# Serial_IO_Interface1.net
KiCad netlist of a schematic drawn in Altium Designer
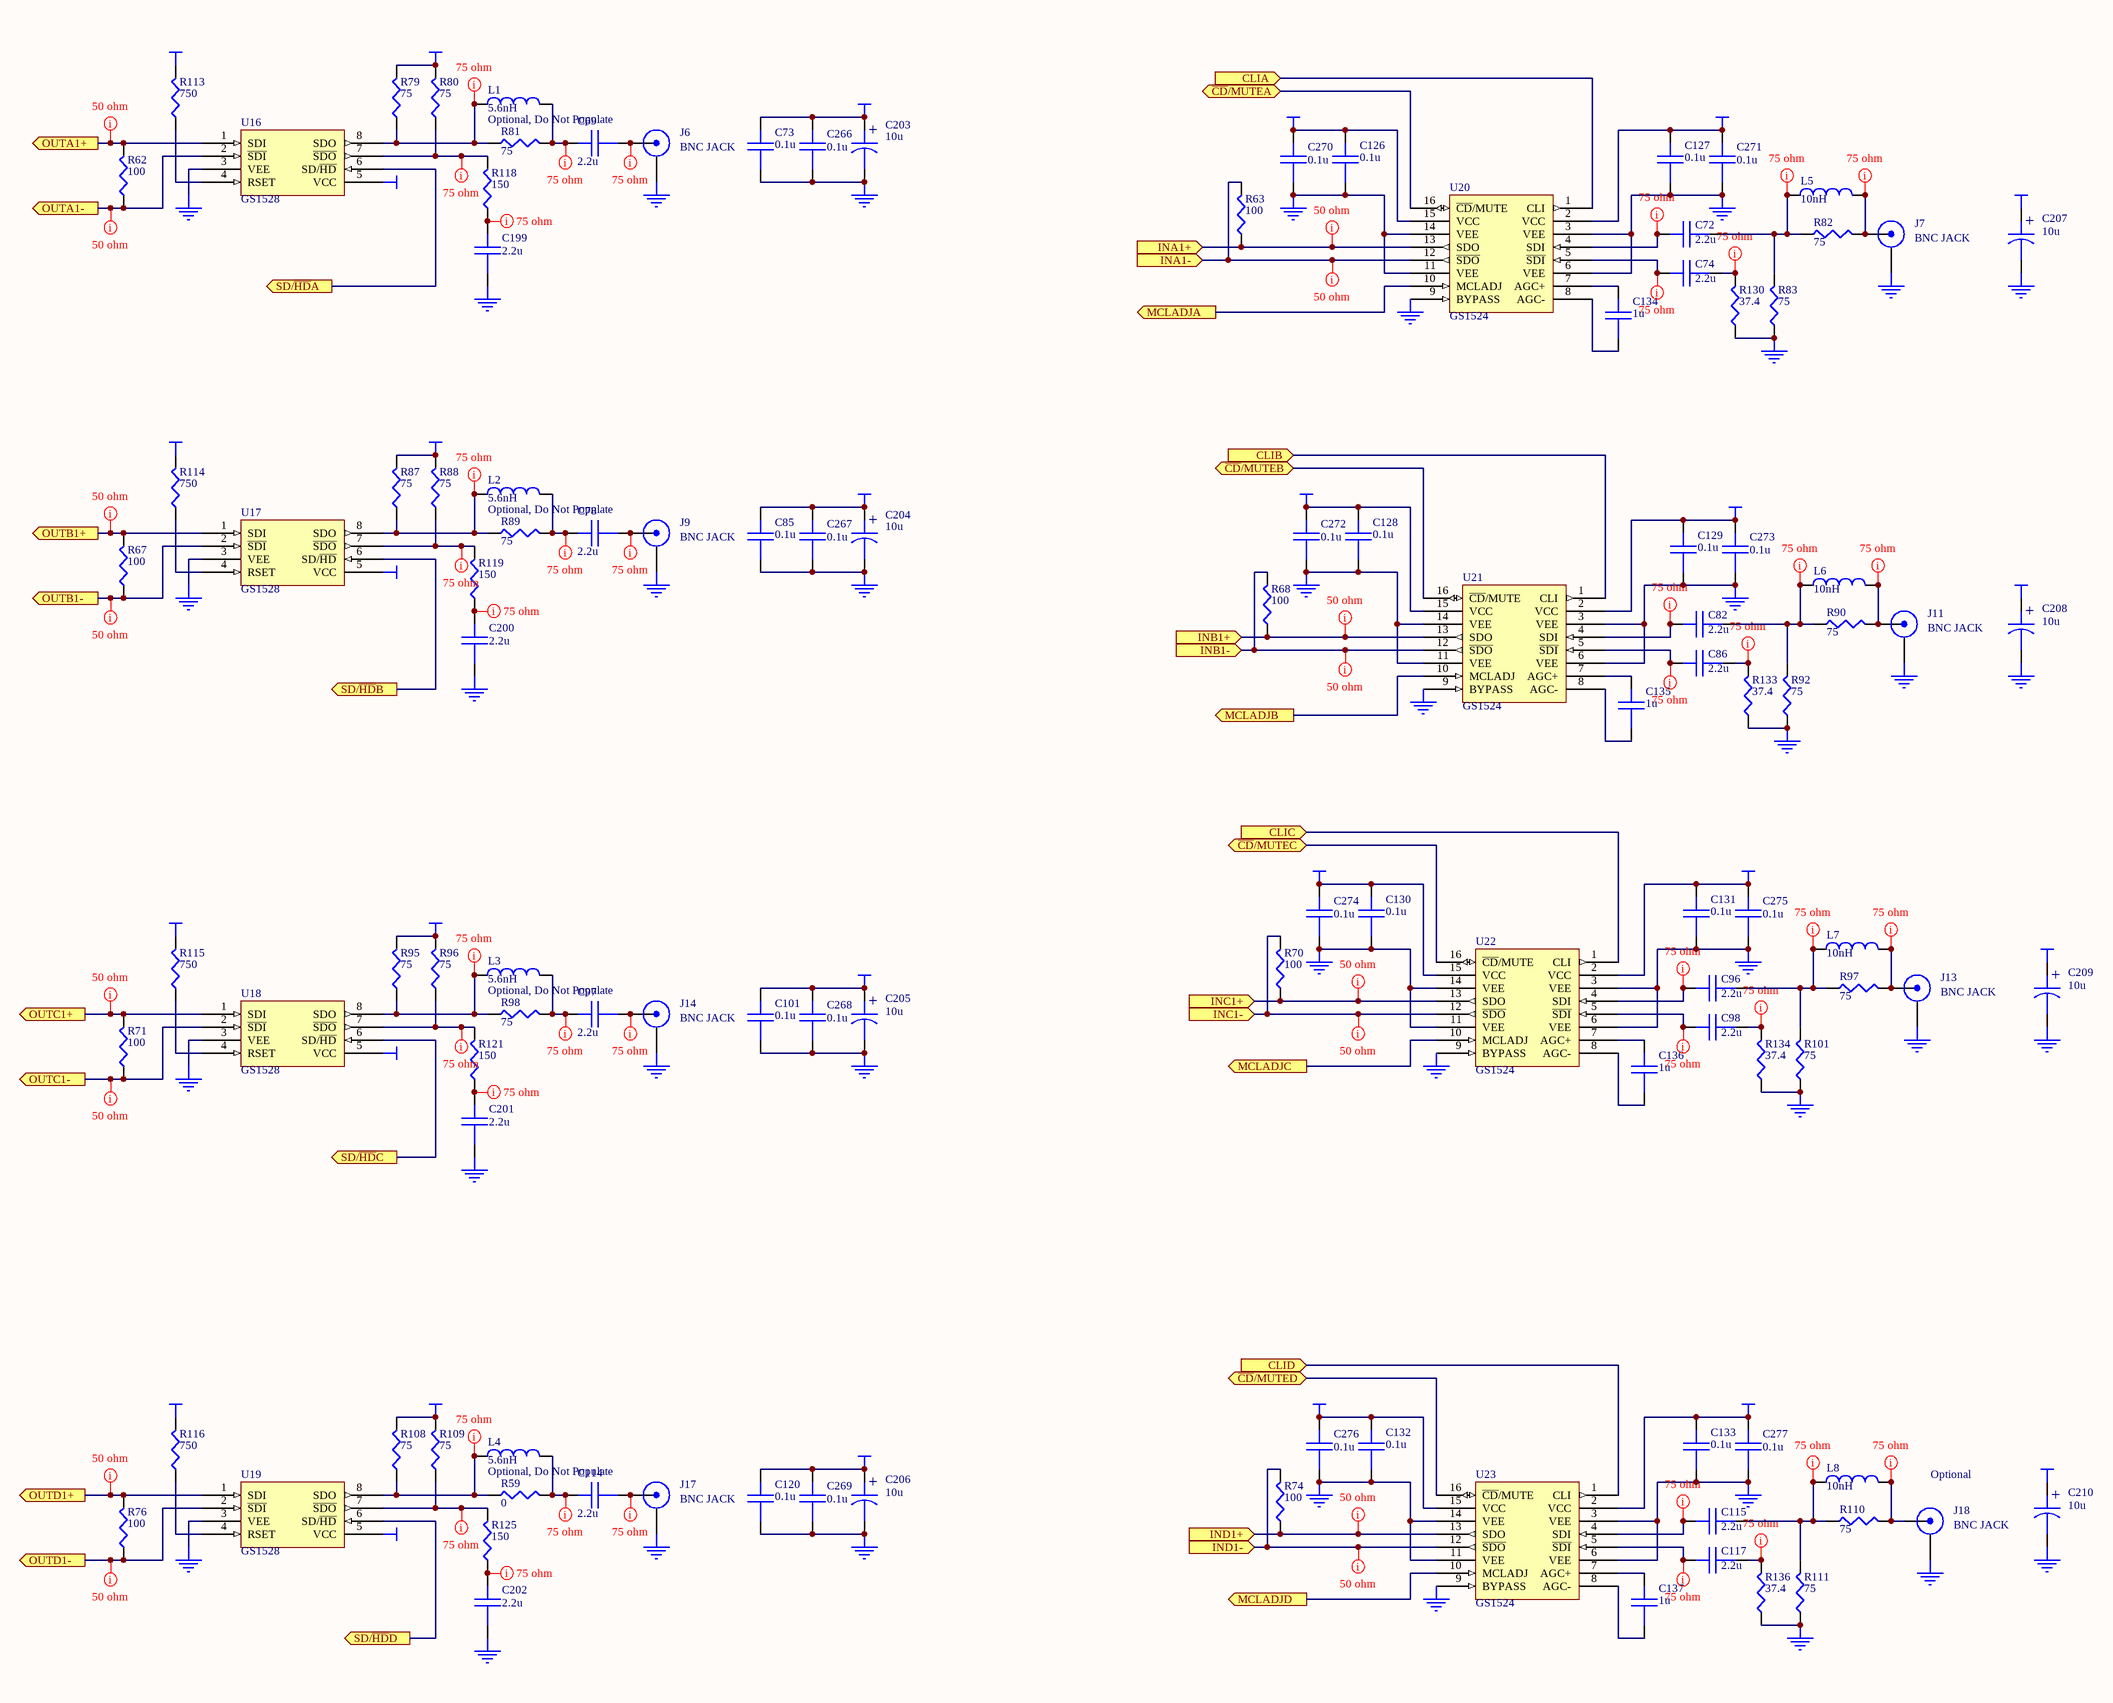
[diagram p0: Serial IO Interface1.SchDoc]

(export (version "E")
  (design (tool "Eeschema 10.0.6"))
  (components
    (comp (ref "C69")
      (value "~")
      (footprint "0603")
      (description "SMT CAP")
      (libsource (lib "Cypress Molson") (part "CAP"))
    )
    (comp (ref "C72")
      (value "~")
      (footprint "0603")
      (description "SMT CAP")
      (libsource (lib "Cypress Molson") (part "CAP"))
    )
    (comp (ref "C73")
      (value "~")
      (footprint "0603")
      (description "SMT CAP")
      (libsource (lib "Cypress Molson") (part "CAP"))
    )
    (comp (ref "C74")
      (value "~")
      (footprint "0603")
      (description "SMT CAP")
      (libsource (lib "Cypress Molson") (part "CAP"))
    )
    (comp (ref "C78")
      (value "~")
      (footprint "0603")
      (description "SMT CAP")
      (libsource (lib "Cypress Molson") (part "CAP"))
    )
    (comp (ref "C82")
      (value "~")
      (footprint "0603")
      (description "SMT CAP")
      (libsource (lib "Cypress Molson") (part "CAP"))
    )
    (comp (ref "C85")
      (value "~")
      (footprint "0603")
      (description "SMT CAP")
      (libsource (lib "Cypress Molson") (part "CAP"))
    )
    (comp (ref "C86")
      (value "~")
      (footprint "0603")
      (description "SMT CAP")
      (libsource (lib "Cypress Molson") (part "CAP"))
    )
    (comp (ref "C96")
      (value "~")
      (footprint "0603")
      (description "SMT CAP")
      (libsource (lib "Cypress Molson") (part "CAP"))
    )
    (comp (ref "C97")
      (value "~")
      (footprint "0603")
      (description "SMT CAP")
      (libsource (lib "Cypress Molson") (part "CAP"))
    )
    (comp (ref "C98")
      (value "~")
      (footprint "0603")
      (description "SMT CAP")
      (libsource (lib "Cypress Molson") (part "CAP"))
    )
    (comp (ref "C101")
      (value "~")
      (footprint "0603")
      (description "SMT CAP")
      (libsource (lib "Cypress Molson") (part "CAP"))
    )
    (comp (ref "C114")
      (value "~")
      (footprint "0603")
      (description "SMT CAP")
      (libsource (lib "Cypress Molson") (part "CAP"))
    )
    (comp (ref "C115")
      (value "~")
      (footprint "0603")
      (description "SMT CAP")
      (libsource (lib "Cypress Molson") (part "CAP"))
    )
    (comp (ref "C117")
      (value "~")
      (footprint "0603")
      (description "SMT CAP")
      (libsource (lib "Cypress Molson") (part "CAP"))
    )
    (comp (ref "C120")
      (value "~")
      (footprint "0603")
      (description "SMT CAP")
      (libsource (lib "Cypress Molson") (part "CAP"))
    )
    (comp (ref "C126")
      (value "0.1u")
      (footprint "0603")
      (description "SMT CAP")
      (libsource (lib "Schematic") (part "CAP"))
    )
    (comp (ref "C127")
      (value "0.1u")
      (footprint "0603")
      (description "SMT CAP")
      (libsource (lib "Schematic") (part "CAP"))
    )
    (comp (ref "C128")
      (value "0.1u")
      (footprint "0603")
      (description "SMT CAP")
      (libsource (lib "Schematic") (part "CAP"))
    )
    (comp (ref "C129")
      (value "0.1u")
      (footprint "0603")
      (description "SMT CAP")
      (libsource (lib "Schematic") (part "CAP"))
    )
    (comp (ref "C130")
      (value "0.1u")
      (footprint "0603")
      (description "SMT CAP")
      (libsource (lib "Schematic") (part "CAP"))
    )
    (comp (ref "C131")
      (value "0.1u")
      (footprint "0603")
      (description "SMT CAP")
      (libsource (lib "Schematic") (part "CAP"))
    )
    (comp (ref "C132")
      (value "0.1u")
      (footprint "0603")
      (description "SMT CAP")
      (libsource (lib "Schematic") (part "CAP"))
    )
    (comp (ref "C133")
      (value "0.1u")
      (footprint "0603")
      (description "SMT CAP")
      (libsource (lib "Schematic") (part "CAP"))
    )
    (comp (ref "C134")
      (value "1u")
      (footprint "0603")
      (description "SMT CAP")
      (libsource (lib "Schematic") (part "CAP"))
    )
    (comp (ref "C135")
      (value "1u")
      (footprint "0603")
      (description "SMT CAP")
      (libsource (lib "Schematic") (part "CAP"))
    )
    (comp (ref "C136")
      (value "1u")
      (footprint "0603")
      (description "SMT CAP")
      (libsource (lib "Schematic") (part "CAP"))
    )
    (comp (ref "C137")
      (value "1u")
      (footprint "0603")
      (description "SMT CAP")
      (libsource (lib "Schematic") (part "CAP"))
    )
    (comp (ref "C199")
      (value "~")
      (footprint "0603")
      (description "SMT CAP")
      (libsource (lib "Cypress Molson") (part "CAP"))
    )
    (comp (ref "C200")
      (value "~")
      (footprint "0603")
      (description "SMT CAP")
      (libsource (lib "Cypress Molson") (part "CAP"))
    )
    (comp (ref "C201")
      (value "~")
      (footprint "0603")
      (description "SMT CAP")
      (libsource (lib "Cypress Molson") (part "CAP"))
    )
    (comp (ref "C202")
      (value "~")
      (footprint "0603")
      (description "SMT CAP")
      (libsource (lib "Cypress Molson") (part "CAP"))
    )
    (comp (ref "C203")
      (value "10u")
      (footprint "6032")
      (libsource (lib "Cypress Molson") (part "CAPACITOR POL"))
    )
    (comp (ref "C204")
      (value "10u")
      (footprint "6032")
      (libsource (lib "Cypress Molson") (part "CAPACITOR POL"))
    )
    (comp (ref "C205")
      (value "10u")
      (footprint "6032")
      (libsource (lib "Cypress Molson") (part "CAPACITOR POL"))
    )
    (comp (ref "C206")
      (value "10u")
      (footprint "6032")
      (libsource (lib "Cypress Molson") (part "CAPACITOR POL"))
    )
    (comp (ref "C207")
      (value "10u")
      (footprint "6032")
      (libsource (lib "Cypress Molson") (part "CAPACITOR POL"))
    )
    (comp (ref "C208")
      (value "10u")
      (footprint "6032")
      (libsource (lib "Cypress Molson") (part "CAPACITOR POL"))
    )
    (comp (ref "C209")
      (value "10u")
      (footprint "6032")
      (libsource (lib "Cypress Molson") (part "CAPACITOR POL"))
    )
    (comp (ref "C210")
      (value "10u")
      (footprint "6032")
      (libsource (lib "Cypress Molson") (part "CAPACITOR POL"))
    )
    (comp (ref "C266")
      (value "~")
      (footprint "0603")
      (description "SMT CAP")
      (libsource (lib "Cypress Molson") (part "CAP"))
    )
    (comp (ref "C267")
      (value "~")
      (footprint "0603")
      (description "SMT CAP")
      (libsource (lib "Cypress Molson") (part "CAP"))
    )
    (comp (ref "C268")
      (value "~")
      (footprint "0603")
      (description "SMT CAP")
      (libsource (lib "Cypress Molson") (part "CAP"))
    )
    (comp (ref "C269")
      (value "~")
      (footprint "0603")
      (description "SMT CAP")
      (libsource (lib "Cypress Molson") (part "CAP"))
    )
    (comp (ref "C270")
      (value "~")
      (footprint "0603")
      (description "SMT CAP")
      (libsource (lib "Cypress Molson") (part "CAP"))
    )
    (comp (ref "C271")
      (value "~")
      (footprint "0603")
      (description "SMT CAP")
      (libsource (lib "Cypress Molson") (part "CAP"))
    )
    (comp (ref "C272")
      (value "~")
      (footprint "0603")
      (description "SMT CAP")
      (libsource (lib "Cypress Molson") (part "CAP"))
    )
    (comp (ref "C273")
      (value "~")
      (footprint "0603")
      (description "SMT CAP")
      (libsource (lib "Cypress Molson") (part "CAP"))
    )
    (comp (ref "C274")
      (value "~")
      (footprint "0603")
      (description "SMT CAP")
      (libsource (lib "Cypress Molson") (part "CAP"))
    )
    (comp (ref "C275")
      (value "~")
      (footprint "0603")
      (description "SMT CAP")
      (libsource (lib "Cypress Molson") (part "CAP"))
    )
    (comp (ref "C276")
      (value "~")
      (footprint "0603")
      (description "SMT CAP")
      (libsource (lib "Cypress Molson") (part "CAP"))
    )
    (comp (ref "C277")
      (value "~")
      (footprint "0603")
      (description "SMT CAP")
      (libsource (lib "Cypress Molson") (part "CAP"))
    )
    (comp (ref "J6")
      (value "BNC JACK")
      (footprint "BNC-EDGE")
      (description "BNC Jack")
      (libsource (lib "Cypress Molson") (part "BNC JACK"))
    )
    (comp (ref "J7")
      (value "BNC JACK")
      (footprint "BNC-EDGE")
      (description "BNC Jack")
      (libsource (lib "Cypress Molson") (part "BNC JACK"))
    )
    (comp (ref "J9")
      (value "BNC JACK")
      (footprint "BNC-EDGE")
      (description "BNC Jack")
      (libsource (lib "Cypress Molson") (part "BNC JACK"))
    )
    (comp (ref "J11")
      (value "BNC JACK")
      (footprint "BNC-EDGE")
      (description "BNC Jack")
      (libsource (lib "Cypress Molson") (part "BNC JACK"))
    )
    (comp (ref "J13")
      (value "BNC JACK")
      (footprint "BNC-EDGE")
      (description "BNC Jack")
      (libsource (lib "Cypress Molson") (part "BNC JACK"))
    )
    (comp (ref "J14")
      (value "BNC JACK")
      (footprint "BNC-EDGE")
      (description "BNC Jack")
      (libsource (lib "Cypress Molson") (part "BNC JACK"))
    )
    (comp (ref "J17")
      (value "BNC JACK")
      (footprint "BNC-EDGE")
      (description "BNC Jack")
      (libsource (lib "Cypress Molson") (part "BNC JACK"))
    )
    (comp (ref "J18")
      (value "BNC JACK")
      (footprint "BNC-EDGE")
      (description "BNC Jack")
      (libsource (lib "Cypress Molson") (part "BNC JACK"))
    )
    (comp (ref "L1")
      (value "5.6nH")
      (footprint "0805")
      (description "Inductor")
      (fields
        (field (name "MANUFACTURER") "Generic Components")
        (field (name "NOTE") "Optional, Do Not Populate")
        (field (name "PUBLISHER") "Altium Limited")
      )
      (libsource (lib "Miscellaneous Devices") (part "Inductor"))
    )
    (comp (ref "L2")
      (value "5.6nH")
      (footprint "0805")
      (description "Inductor")
      (fields
        (field (name "MANUFACTURER") "Generic Components")
        (field (name "NOTE") "Optional, Do Not Populate")
        (field (name "PUBLISHER") "Altium Limited")
      )
      (libsource (lib "Miscellaneous Devices") (part "Inductor"))
    )
    (comp (ref "L3")
      (value "5.6nH")
      (footprint "0805")
      (description "Inductor")
      (fields
        (field (name "MANUFACTURER") "Generic Components")
        (field (name "NOTE") "Optional, Do Not Populate")
        (field (name "PUBLISHER") "Altium Limited")
      )
      (libsource (lib "Miscellaneous Devices") (part "Inductor"))
    )
    (comp (ref "L4")
      (value "5.6nH")
      (footprint "0805")
      (description "Inductor")
      (fields
        (field (name "MANUFACTURER") "Generic Components")
        (field (name "NOTE") "Optional, Do Not Populate")
        (field (name "PUBLISHER") "Altium Limited")
      )
      (libsource (lib "Miscellaneous Devices") (part "Inductor"))
    )
    (comp (ref "L5")
      (value "10nH")
      (footprint "0805")
      (description "Inductor")
      (fields (field (name "MANUFACTURER") "Generic Components") (field (name "PUBLISHER") "Altium Limited"))
      (libsource (lib "Miscellaneous Devices") (part "Inductor"))
    )
    (comp (ref "L6")
      (value "10nH")
      (footprint "0805")
      (description "Inductor")
      (fields (field (name "MANUFACTURER") "Generic Components") (field (name "PUBLISHER") "Altium Limited"))
      (libsource (lib "Miscellaneous Devices") (part "Inductor"))
    )
    (comp (ref "L7")
      (value "10nH")
      (footprint "0805")
      (description "Inductor")
      (fields (field (name "MANUFACTURER") "Generic Components") (field (name "PUBLISHER") "Altium Limited"))
      (libsource (lib "Miscellaneous Devices") (part "Inductor"))
    )
    (comp (ref "L8")
      (value "10nH")
      (footprint "0805")
      (description "Inductor")
      (fields (field (name "MANUFACTURER") "Generic Components") (field (name "PUBLISHER") "Altium Limited"))
      (libsource (lib "Miscellaneous Devices") (part "Inductor"))
    )
    (comp (ref "R59") (value "0") (footprint "0603") (libsource (lib "Cypress Molson") (part "RES1")))
    (comp (ref "R62") (value "100") (footprint "0603") (libsource (lib "Cypress Molson") (part "RES1")))
    (comp (ref "R63") (value "100") (footprint "0603") (libsource (lib "Cypress Molson") (part "RES1")))
    (comp (ref "R67") (value "100") (footprint "0603") (libsource (lib "Cypress Molson") (part "RES1")))
    (comp (ref "R68") (value "100") (footprint "0603") (libsource (lib "Cypress Molson") (part "RES1")))
    (comp (ref "R70") (value "100") (footprint "0603") (libsource (lib "Cypress Molson") (part "RES1")))
    (comp (ref "R71") (value "100") (footprint "0603") (libsource (lib "Cypress Molson") (part "RES1")))
    (comp (ref "R74") (value "100") (footprint "0603") (libsource (lib "Cypress Molson") (part "RES1")))
    (comp (ref "R76") (value "100") (footprint "0603") (libsource (lib "Cypress Molson") (part "RES1")))
    (comp (ref "R79") (value "75") (footprint "0603") (libsource (lib "Cypress Molson") (part "RES1")))
    (comp (ref "R80") (value "75") (footprint "0603") (libsource (lib "Cypress Molson") (part "RES1")))
    (comp (ref "R81") (value "75") (footprint "0603") (libsource (lib "Cypress Molson") (part "RES1")))
    (comp (ref "R82") (value "75") (footprint "0603") (libsource (lib "Cypress Molson") (part "RES1")))
    (comp (ref "R83") (value "75") (footprint "0603") (libsource (lib "Cypress Molson") (part "RES1")))
    (comp (ref "R87") (value "75") (footprint "0603") (libsource (lib "Cypress Molson") (part "RES1")))
    (comp (ref "R88") (value "75") (footprint "0603") (libsource (lib "Cypress Molson") (part "RES1")))
    (comp (ref "R89") (value "75") (footprint "0603") (libsource (lib "Cypress Molson") (part "RES1")))
    (comp (ref "R90") (value "75") (footprint "0603") (libsource (lib "Cypress Molson") (part "RES1")))
    (comp (ref "R92") (value "75") (footprint "0603") (libsource (lib "Cypress Molson") (part "RES1")))
    (comp (ref "R95") (value "75") (footprint "0603") (libsource (lib "Cypress Molson") (part "RES1")))
    (comp (ref "R96") (value "75") (footprint "0603") (libsource (lib "Cypress Molson") (part "RES1")))
    (comp (ref "R97") (value "75") (footprint "0603") (libsource (lib "Cypress Molson") (part "RES1")))
    (comp (ref "R98") (value "75") (footprint "0603") (libsource (lib "Cypress Molson") (part "RES1")))
    (comp (ref "R101") (value "75") (footprint "0603") (libsource (lib "Cypress Molson") (part "RES1")))
    (comp (ref "R108") (value "75") (footprint "0603") (libsource (lib "Cypress Molson") (part "RES1")))
    (comp (ref "R109") (value "75") (footprint "0603") (libsource (lib "Cypress Molson") (part "RES1")))
    (comp (ref "R110") (value "75") (footprint "0603") (libsource (lib "Cypress Molson") (part "RES1")))
    (comp (ref "R111") (value "75") (footprint "0603") (libsource (lib "Cypress Molson") (part "RES1")))
    (comp (ref "R113") (value "750") (footprint "0603") (libsource (lib "Cypress Molson") (part "RES1")))
    (comp (ref "R114") (value "750") (footprint "0603") (libsource (lib "Cypress Molson") (part "RES1")))
    (comp (ref "R115") (value "750") (footprint "0603") (libsource (lib "Cypress Molson") (part "RES1")))
    (comp (ref "R116") (value "750") (footprint "0603") (libsource (lib "Cypress Molson") (part "RES1")))
    (comp (ref "R118") (value "150") (footprint "0603") (libsource (lib "Cypress Molson") (part "RES1")))
    (comp (ref "R119") (value "150") (footprint "0603") (libsource (lib "Cypress Molson") (part "RES1")))
    (comp (ref "R121") (value "150") (footprint "0603") (libsource (lib "Cypress Molson") (part "RES1")))
    (comp (ref "R125") (value "150") (footprint "0603") (libsource (lib "Cypress Molson") (part "RES1")))
    (comp (ref "R130") (value "37.4") (footprint "0603") (libsource (lib "Cypress Molson") (part "RES1")))
    (comp (ref "R133") (value "37.4") (footprint "0603") (libsource (lib "Cypress Molson") (part "RES1")))
    (comp (ref "R134") (value "37.4") (footprint "0603") (libsource (lib "Cypress Molson") (part "RES1")))
    (comp (ref "R136") (value "37.4") (footprint "0603") (libsource (lib "Cypress Molson") (part "RES1")))
    (comp (ref "U16")
      (value "GS1528")
      (footprint "SO-8")
      (description "HD-LINX II Multi-Rate SDI Dual Slew-Rate Cable Driver")
      (libsource (lib "Cypress Molson") (part "GS1528"))
    )
    (comp (ref "U17")
      (value "GS1528")
      (footprint "SO-8")
      (description "HD-LINX II Multi-Rate SDI Dual Slew-Rate Cable Driver")
      (libsource (lib "Cypress Molson") (part "GS1528"))
    )
    (comp (ref "U18")
      (value "GS1528")
      (footprint "SO-8")
      (description "HD-LINX II Multi-Rate SDI Dual Slew-Rate Cable Driver")
      (libsource (lib "Cypress Molson") (part "GS1528"))
    )
    (comp (ref "U19")
      (value "GS1528")
      (footprint "SO-8")
      (description "HD-LINX II Multi-Rate SDI Dual Slew-Rate Cable Driver")
      (libsource (lib "Cypress Molson") (part "GS1528"))
    )
    (comp (ref "U20")
      (value "GS1524")
      (footprint "SO-16")
      (description "HD-LINX II Multi-Rate SDI Adaptive Cable Equalizer")
      (libsource (lib "Cypress Molson") (part "GS1524"))
    )
    (comp (ref "U21")
      (value "GS1524")
      (footprint "SO-16")
      (description "HD-LINX II Multi-Rate SDI Adaptive Cable Equalizer")
      (libsource (lib "Cypress Molson") (part "GS1524"))
    )
    (comp (ref "U22")
      (value "GS1524")
      (footprint "SO-16")
      (description "HD-LINX II Multi-Rate SDI Adaptive Cable Equalizer")
      (libsource (lib "Cypress Molson") (part "GS1524"))
    )
    (comp (ref "U23")
      (value "GS1524")
      (footprint "SO-16")
      (description "HD-LINX II Multi-Rate SDI Adaptive Cable Equalizer")
      (libsource (lib "Cypress Molson") (part "GS1524"))
    )
  )
  (nets
    (net (code "1") (name "+3.3V") (class "Default")
      (node (ref "C101") (pin "1") (pinfunction "1_1") (pintype "passive"))
      (node (ref "C120") (pin "1") (pinfunction "1_1") (pintype "passive"))
      (node (ref "C126") (pin "1") (pinfunction "1_1") (pintype "passive"))
      (node (ref "C127") (pin "1") (pinfunction "1_1") (pintype "passive"))
      (node (ref "C128") (pin "1") (pinfunction "1_1") (pintype "passive"))
      (node (ref "C129") (pin "1") (pinfunction "1_1") (pintype "passive"))
      (node (ref "C130") (pin "1") (pinfunction "1_1") (pintype "passive"))
      (node (ref "C131") (pin "1") (pinfunction "1_1") (pintype "passive"))
      (node (ref "C132") (pin "1") (pinfunction "1_1") (pintype "passive"))
      (node (ref "C133") (pin "1") (pinfunction "1_1") (pintype "passive"))
      (node (ref "C203") (pin "1") (pinfunction "1_1") (pintype "passive"))
      (node (ref "C204") (pin "1") (pinfunction "1_1") (pintype "passive"))
      (node (ref "C205") (pin "1") (pinfunction "1_1") (pintype "passive"))
      (node (ref "C206") (pin "1") (pinfunction "1_1") (pintype "passive"))
      (node (ref "C207") (pin "1") (pinfunction "1_1") (pintype "passive"))
      (node (ref "C208") (pin "1") (pinfunction "1_1") (pintype "passive"))
      (node (ref "C209") (pin "1") (pinfunction "1_1") (pintype "passive"))
      (node (ref "C210") (pin "1") (pinfunction "1_1") (pintype "passive"))
      (node (ref "C266") (pin "1") (pinfunction "1_1") (pintype "passive"))
      (node (ref "C267") (pin "1") (pinfunction "1_1") (pintype "passive"))
      (node (ref "C268") (pin "1") (pinfunction "1_1") (pintype "passive"))
      (node (ref "C269") (pin "1") (pinfunction "1_1") (pintype "passive"))
      (node (ref "C270") (pin "1") (pinfunction "1_1") (pintype "passive"))
      (node (ref "C271") (pin "1") (pinfunction "1_1") (pintype "passive"))
      (node (ref "C272") (pin "1") (pinfunction "1_1") (pintype "passive"))
      (node (ref "C273") (pin "1") (pinfunction "1_1") (pintype "passive"))
      (node (ref "C274") (pin "1") (pinfunction "1_1") (pintype "passive"))
      (node (ref "C275") (pin "1") (pinfunction "1_1") (pintype "passive"))
      (node (ref "C276") (pin "1") (pinfunction "1_1") (pintype "passive"))
      (node (ref "C277") (pin "1") (pinfunction "1_1") (pintype "passive"))
      (node (ref "C73") (pin "1") (pinfunction "1_1") (pintype "passive"))
      (node (ref "C85") (pin "1") (pinfunction "1_1") (pintype "passive"))
      (node (ref "R108") (pin "2") (pintype "passive"))
      (node (ref "R109") (pin "2") (pintype "passive"))
      (node (ref "R113") (pin "2") (pintype "passive"))
      (node (ref "R114") (pin "2") (pintype "passive"))
      (node (ref "R115") (pin "2") (pintype "passive"))
      (node (ref "R116") (pin "2") (pintype "passive"))
      (node (ref "R79") (pin "2") (pintype "passive"))
      (node (ref "R80") (pin "2") (pintype "passive"))
      (node (ref "R87") (pin "2") (pintype "passive"))
      (node (ref "R88") (pin "2") (pintype "passive"))
      (node (ref "R95") (pin "2") (pintype "passive"))
      (node (ref "R96") (pin "2") (pintype "passive"))
      (node (ref "U16") (pin "5") (pinfunction "VCC_5") (pintype "power_in"))
      (node (ref "U17") (pin "5") (pinfunction "VCC_5") (pintype "power_in"))
      (node (ref "U18") (pin "5") (pinfunction "VCC_5") (pintype "power_in"))
      (node (ref "U19") (pin "5") (pinfunction "VCC_5") (pintype "power_in"))
      (node (ref "U20") (pin "15") (pinfunction "VCC_15") (pintype "power_in"))
      (node (ref "U20") (pin "2") (pinfunction "VCC_2") (pintype "power_in"))
      (node (ref "U21") (pin "15") (pinfunction "VCC_15") (pintype "power_in"))
      (node (ref "U21") (pin "2") (pinfunction "VCC_2") (pintype "power_in"))
      (node (ref "U22") (pin "15") (pinfunction "VCC_15") (pintype "power_in"))
      (node (ref "U22") (pin "2") (pinfunction "VCC_2") (pintype "power_in"))
      (node (ref "U23") (pin "15") (pinfunction "VCC_15") (pintype "power_in"))
      (node (ref "U23") (pin "2") (pinfunction "VCC_2") (pintype "power_in"))
    )
    (net (code "2") (name "/CLIA") (class "Default")
      (node (ref "U20") (pin "1") (pinfunction "CLI_1") (pintype "output"))
    )
    (net (code "3") (name "/CLIB") (class "Default")
      (node (ref "U21") (pin "1") (pinfunction "CLI_1") (pintype "output"))
    )
    (net (code "4") (name "/CLIC") (class "Default")
      (node (ref "U22") (pin "1") (pinfunction "CLI_1") (pintype "output"))
    )
    (net (code "5") (name "/CLID") (class "Default")
      (node (ref "U23") (pin "1") (pinfunction "CLI_1") (pintype "output"))
    )
    (net (code "6") (name "/INA1+") (class "Default")
      (node (ref "R63") (pin "1") (pintype "passive"))
      (node (ref "U20") (pin "13") (pinfunction "SDO_13") (pintype "output"))
    )
    (net (code "7") (name "/INA1-") (class "Default")
      (node (ref "R63") (pin "2") (pintype "passive"))
      (node (ref "U20") (pin "12") (pinfunction "~{SDO}_12") (pintype "output"))
    )
    (net (code "8") (name "/INB1+") (class "Default")
      (node (ref "R68") (pin "1") (pintype "passive"))
      (node (ref "U21") (pin "13") (pinfunction "SDO_13") (pintype "output"))
    )
    (net (code "9") (name "/INB1-") (class "Default")
      (node (ref "R68") (pin "2") (pintype "passive"))
      (node (ref "U21") (pin "12") (pinfunction "~{SDO}_12") (pintype "output"))
    )
    (net (code "10") (name "/INC1+") (class "Default")
      (node (ref "R70") (pin "1") (pintype "passive"))
      (node (ref "U22") (pin "13") (pinfunction "SDO_13") (pintype "output"))
    )
    (net (code "11") (name "/INC1-") (class "Default")
      (node (ref "R70") (pin "2") (pintype "passive"))
      (node (ref "U22") (pin "12") (pinfunction "~{SDO}_12") (pintype "output"))
    )
    (net (code "12") (name "/IND1+") (class "Default")
      (node (ref "R74") (pin "1") (pintype "passive"))
      (node (ref "U23") (pin "13") (pinfunction "SDO_13") (pintype "output"))
    )
    (net (code "13") (name "/IND1-") (class "Default")
      (node (ref "R74") (pin "2") (pintype "passive"))
      (node (ref "U23") (pin "12") (pinfunction "~{SDO}_12") (pintype "output"))
    )
    (net (code "14") (name "/MCLADJA") (class "Default")
      (node (ref "U20") (pin "10") (pinfunction "MCLADJ_10") (pintype "input"))
    )
    (net (code "15") (name "/MCLADJB") (class "Default")
      (node (ref "U21") (pin "10") (pinfunction "MCLADJ_10") (pintype "input"))
    )
    (net (code "16") (name "/MCLADJC") (class "Default")
      (node (ref "U22") (pin "10") (pinfunction "MCLADJ_10") (pintype "input"))
    )
    (net (code "17") (name "/MCLADJD") (class "Default")
      (node (ref "U23") (pin "10") (pinfunction "MCLADJ_10") (pintype "input"))
    )
    (net (code "18") (name "/OUTA1+") (class "Default")
      (node (ref "R62") (pin "2") (pintype "passive"))
      (node (ref "U16") (pin "1") (pinfunction "SDI_1") (pintype "input"))
    )
    (net (code "19") (name "/OUTA1-") (class "Default")
      (node (ref "R62") (pin "1") (pintype "passive"))
      (node (ref "U16") (pin "2") (pinfunction "~{SDI}_2") (pintype "input"))
    )
    (net (code "20") (name "/OUTB1+") (class "Default")
      (node (ref "R67") (pin "2") (pintype "passive"))
      (node (ref "U17") (pin "1") (pinfunction "SDI_1") (pintype "input"))
    )
    (net (code "21") (name "/OUTB1-") (class "Default")
      (node (ref "R67") (pin "1") (pintype "passive"))
      (node (ref "U17") (pin "2") (pinfunction "~{SDI}_2") (pintype "input"))
    )
    (net (code "22") (name "/OUTC1+") (class "Default")
      (node (ref "R71") (pin "2") (pintype "passive"))
      (node (ref "U18") (pin "1") (pinfunction "SDI_1") (pintype "input"))
    )
    (net (code "23") (name "/OUTC1-") (class "Default")
      (node (ref "R71") (pin "1") (pintype "passive"))
      (node (ref "U18") (pin "2") (pinfunction "~{SDI}_2") (pintype "input"))
    )
    (net (code "24") (name "/OUTD1+") (class "Default")
      (node (ref "R76") (pin "2") (pintype "passive"))
      (node (ref "U19") (pin "1") (pinfunction "SDI_1") (pintype "input"))
    )
    (net (code "25") (name "/OUTD1-") (class "Default")
      (node (ref "R76") (pin "1") (pintype "passive"))
      (node (ref "U19") (pin "2") (pinfunction "~{SDI}_2") (pintype "input"))
    )
    (net (code "26") (name "/SD{slash}~{HD}A") (class "Default")
      (node (ref "U16") (pin "6") (pinfunction "SD/~{HD}_6") (pintype "input"))
    )
    (net (code "27") (name "/SD{slash}~{HD}B") (class "Default")
      (node (ref "U17") (pin "6") (pinfunction "SD/~{HD}_6") (pintype "input"))
    )
    (net (code "28") (name "/SD{slash}~{HD}C") (class "Default")
      (node (ref "U18") (pin "6") (pinfunction "SD/~{HD}_6") (pintype "input"))
    )
    (net (code "29") (name "/SD{slash}~{HD}D") (class "Default")
      (node (ref "U19") (pin "6") (pinfunction "SD/~{HD}_6") (pintype "input"))
    )
    (net (code "30") (name "/~{CD}{slash}MUTEA") (class "Default")
      (node (ref "U20") (pin "16") (pinfunction "~{CD}/MUTE_16") (pintype "bidirectional"))
    )
    (net (code "31") (name "/~{CD}{slash}MUTEB") (class "Default")
      (node (ref "U21") (pin "16") (pinfunction "~{CD}/MUTE_16") (pintype "bidirectional"))
    )
    (net (code "32") (name "/~{CD}{slash}MUTEC") (class "Default")
      (node (ref "U22") (pin "16") (pinfunction "~{CD}/MUTE_16") (pintype "bidirectional"))
    )
    (net (code "33") (name "/~{CD}{slash}MUTED") (class "Default")
      (node (ref "U23") (pin "16") (pinfunction "~{CD}/MUTE_16") (pintype "bidirectional"))
    )
    (net (code "34") (name "GND") (class "Default")
      (node (ref "C101") (pin "2") (pinfunction "2_2") (pintype "passive"))
      (node (ref "C120") (pin "2") (pinfunction "2_2") (pintype "passive"))
      (node (ref "C126") (pin "2") (pinfunction "2_2") (pintype "passive"))
      (node (ref "C127") (pin "2") (pinfunction "2_2") (pintype "passive"))
      (node (ref "C128") (pin "2") (pinfunction "2_2") (pintype "passive"))
      (node (ref "C129") (pin "2") (pinfunction "2_2") (pintype "passive"))
      (node (ref "C130") (pin "2") (pinfunction "2_2") (pintype "passive"))
      (node (ref "C131") (pin "2") (pinfunction "2_2") (pintype "passive"))
      (node (ref "C132") (pin "2") (pinfunction "2_2") (pintype "passive"))
      (node (ref "C133") (pin "2") (pinfunction "2_2") (pintype "passive"))
      (node (ref "C199") (pin "2") (pinfunction "2_2") (pintype "passive"))
      (node (ref "C200") (pin "2") (pinfunction "2_2") (pintype "passive"))
      (node (ref "C201") (pin "2") (pinfunction "2_2") (pintype "passive"))
      (node (ref "C202") (pin "2") (pinfunction "2_2") (pintype "passive"))
      (node (ref "C203") (pin "2") (pinfunction "2_2") (pintype "passive"))
      (node (ref "C204") (pin "2") (pinfunction "2_2") (pintype "passive"))
      (node (ref "C205") (pin "2") (pinfunction "2_2") (pintype "passive"))
      (node (ref "C206") (pin "2") (pinfunction "2_2") (pintype "passive"))
      (node (ref "C207") (pin "2") (pinfunction "2_2") (pintype "passive"))
      (node (ref "C208") (pin "2") (pinfunction "2_2") (pintype "passive"))
      (node (ref "C209") (pin "2") (pinfunction "2_2") (pintype "passive"))
      (node (ref "C210") (pin "2") (pinfunction "2_2") (pintype "passive"))
      (node (ref "C266") (pin "2") (pinfunction "2_2") (pintype "passive"))
      (node (ref "C267") (pin "2") (pinfunction "2_2") (pintype "passive"))
      (node (ref "C268") (pin "2") (pinfunction "2_2") (pintype "passive"))
      (node (ref "C269") (pin "2") (pinfunction "2_2") (pintype "passive"))
      (node (ref "C270") (pin "2") (pinfunction "2_2") (pintype "passive"))
      (node (ref "C271") (pin "2") (pinfunction "2_2") (pintype "passive"))
      (node (ref "C272") (pin "2") (pinfunction "2_2") (pintype "passive"))
      (node (ref "C273") (pin "2") (pinfunction "2_2") (pintype "passive"))
      (node (ref "C274") (pin "2") (pinfunction "2_2") (pintype "passive"))
      (node (ref "C275") (pin "2") (pinfunction "2_2") (pintype "passive"))
      (node (ref "C276") (pin "2") (pinfunction "2_2") (pintype "passive"))
      (node (ref "C277") (pin "2") (pinfunction "2_2") (pintype "passive"))
      (node (ref "C73") (pin "2") (pinfunction "2_2") (pintype "passive"))
      (node (ref "C85") (pin "2") (pinfunction "2_2") (pintype "passive"))
      (node (ref "J11") (pin "2") (pinfunction "GND_2") (pintype "passive"))
      (node (ref "J13") (pin "2") (pinfunction "GND_2") (pintype "passive"))
      (node (ref "J14") (pin "2") (pinfunction "GND_2") (pintype "passive"))
      (node (ref "J17") (pin "2") (pinfunction "GND_2") (pintype "passive"))
      (node (ref "J18") (pin "2") (pinfunction "GND_2") (pintype "passive"))
      (node (ref "J6") (pin "2") (pinfunction "GND_2") (pintype "passive"))
      (node (ref "J7") (pin "2") (pinfunction "GND_2") (pintype "passive"))
      (node (ref "J9") (pin "2") (pinfunction "GND_2") (pintype "passive"))
      (node (ref "R101") (pin "1") (pintype "passive"))
      (node (ref "R111") (pin "1") (pintype "passive"))
      (node (ref "R130") (pin "1") (pintype "passive"))
      (node (ref "R133") (pin "1") (pintype "passive"))
      (node (ref "R134") (pin "1") (pintype "passive"))
      (node (ref "R136") (pin "1") (pintype "passive"))
      (node (ref "R83") (pin "1") (pintype "passive"))
      (node (ref "R92") (pin "1") (pintype "passive"))
      (node (ref "U16") (pin "3") (pinfunction "VEE_3") (pintype "power_in"))
      (node (ref "U17") (pin "3") (pinfunction "VEE_3") (pintype "power_in"))
      (node (ref "U18") (pin "3") (pinfunction "VEE_3") (pintype "power_in"))
      (node (ref "U19") (pin "3") (pinfunction "VEE_3") (pintype "power_in"))
      (node (ref "U20") (pin "11") (pinfunction "VEE_11") (pintype "power_in"))
      (node (ref "U20") (pin "14") (pinfunction "VEE_14") (pintype "power_in"))
      (node (ref "U20") (pin "3") (pinfunction "VEE_3") (pintype "power_in"))
      (node (ref "U20") (pin "6") (pinfunction "VEE_6") (pintype "power_in"))
      (node (ref "U20") (pin "9") (pinfunction "BYPASS_9") (pintype "input"))
      (node (ref "U21") (pin "11") (pinfunction "VEE_11") (pintype "power_in"))
      (node (ref "U21") (pin "14") (pinfunction "VEE_14") (pintype "power_in"))
      (node (ref "U21") (pin "3") (pinfunction "VEE_3") (pintype "power_in"))
      (node (ref "U21") (pin "6") (pinfunction "VEE_6") (pintype "power_in"))
      (node (ref "U21") (pin "9") (pinfunction "BYPASS_9") (pintype "input"))
      (node (ref "U22") (pin "11") (pinfunction "VEE_11") (pintype "power_in"))
      (node (ref "U22") (pin "14") (pinfunction "VEE_14") (pintype "power_in"))
      (node (ref "U22") (pin "3") (pinfunction "VEE_3") (pintype "power_in"))
      (node (ref "U22") (pin "6") (pinfunction "VEE_6") (pintype "power_in"))
      (node (ref "U22") (pin "9") (pinfunction "BYPASS_9") (pintype "input"))
      (node (ref "U23") (pin "11") (pinfunction "VEE_11") (pintype "power_in"))
      (node (ref "U23") (pin "14") (pinfunction "VEE_14") (pintype "power_in"))
      (node (ref "U23") (pin "3") (pinfunction "VEE_3") (pintype "power_in"))
      (node (ref "U23") (pin "6") (pinfunction "VEE_6") (pintype "power_in"))
      (node (ref "U23") (pin "9") (pinfunction "BYPASS_9") (pintype "input"))
    )
    (net (code "35") (name "Net-(C69-Pad1)") (class "Default")
      (node (ref "C69") (pin "1") (pinfunction "1_1") (pintype "passive"))
      (node (ref "L1") (pin "2") (pinfunction "2_2") (pintype "passive"))
      (node (ref "R81") (pin "2") (pintype "passive"))
    )
    (net (code "36") (name "Net-(C72-Pad2)") (class "Default")
      (node (ref "C72") (pin "2") (pinfunction "2_2") (pintype "passive"))
      (node (ref "L5") (pin "1") (pinfunction "1_1") (pintype "passive"))
      (node (ref "R82") (pin "1") (pintype "passive"))
      (node (ref "R83") (pin "2") (pintype "passive"))
    )
    (net (code "37") (name "Net-(C74-Pad2)") (class "Default")
      (node (ref "C74") (pin "2") (pinfunction "2_2") (pintype "passive"))
      (node (ref "R130") (pin "2") (pintype "passive"))
    )
    (net (code "38") (name "Net-(C78-Pad1)") (class "Default")
      (node (ref "C78") (pin "1") (pinfunction "1_1") (pintype "passive"))
      (node (ref "L2") (pin "2") (pinfunction "2_2") (pintype "passive"))
      (node (ref "R89") (pin "2") (pintype "passive"))
    )
    (net (code "39") (name "Net-(C82-Pad2)") (class "Default")
      (node (ref "C82") (pin "2") (pinfunction "2_2") (pintype "passive"))
      (node (ref "L6") (pin "1") (pinfunction "1_1") (pintype "passive"))
      (node (ref "R90") (pin "1") (pintype "passive"))
      (node (ref "R92") (pin "2") (pintype "passive"))
    )
    (net (code "40") (name "Net-(C86-Pad2)") (class "Default")
      (node (ref "C86") (pin "2") (pinfunction "2_2") (pintype "passive"))
      (node (ref "R133") (pin "2") (pintype "passive"))
    )
    (net (code "41") (name "Net-(C96-Pad2)") (class "Default")
      (node (ref "C96") (pin "2") (pinfunction "2_2") (pintype "passive"))
      (node (ref "L7") (pin "1") (pinfunction "1_1") (pintype "passive"))
      (node (ref "R101") (pin "2") (pintype "passive"))
      (node (ref "R97") (pin "1") (pintype "passive"))
    )
    (net (code "42") (name "Net-(C97-Pad1)") (class "Default")
      (node (ref "C97") (pin "1") (pinfunction "1_1") (pintype "passive"))
      (node (ref "L3") (pin "2") (pinfunction "2_2") (pintype "passive"))
      (node (ref "R98") (pin "2") (pintype "passive"))
    )
    (net (code "43") (name "Net-(C98-Pad2)") (class "Default")
      (node (ref "C98") (pin "2") (pinfunction "2_2") (pintype "passive"))
      (node (ref "R134") (pin "2") (pintype "passive"))
    )
    (net (code "44") (name "Net-(C114-Pad1)") (class "Default")
      (node (ref "C114") (pin "1") (pinfunction "1_1") (pintype "passive"))
      (node (ref "L4") (pin "2") (pinfunction "2_2") (pintype "passive"))
      (node (ref "R59") (pin "2") (pintype "passive"))
    )
    (net (code "45") (name "Net-(C115-Pad2)") (class "Default")
      (node (ref "C115") (pin "2") (pinfunction "2_2") (pintype "passive"))
      (node (ref "L8") (pin "1") (pinfunction "1_1") (pintype "passive"))
      (node (ref "R110") (pin "1") (pintype "passive"))
      (node (ref "R111") (pin "2") (pintype "passive"))
    )
    (net (code "46") (name "Net-(C117-Pad2)") (class "Default")
      (node (ref "C117") (pin "2") (pinfunction "2_2") (pintype "passive"))
      (node (ref "R136") (pin "2") (pintype "passive"))
    )
    (net (code "47") (name "Net-(C199-Pad1)") (class "Default")
      (node (ref "C199") (pin "1") (pinfunction "1_1") (pintype "passive"))
      (node (ref "R118") (pin "1") (pintype "passive"))
    )
    (net (code "48") (name "Net-(C200-Pad1)") (class "Default")
      (node (ref "C200") (pin "1") (pinfunction "1_1") (pintype "passive"))
      (node (ref "R119") (pin "1") (pintype "passive"))
    )
    (net (code "49") (name "Net-(C201-Pad1)") (class "Default")
      (node (ref "C201") (pin "1") (pinfunction "1_1") (pintype "passive"))
      (node (ref "R121") (pin "1") (pintype "passive"))
    )
    (net (code "50") (name "Net-(C202-Pad1)") (class "Default")
      (node (ref "C202") (pin "1") (pinfunction "1_1") (pintype "passive"))
      (node (ref "R125") (pin "1") (pintype "passive"))
    )
    (net (code "51") (name "Net-(J6-SIGNAL)") (class "Default")
      (node (ref "C69") (pin "2") (pinfunction "2_2") (pintype "passive"))
      (node (ref "J6") (pin "1") (pinfunction "SIGNAL_1") (pintype "passive"))
    )
    (net (code "52") (name "Net-(J7-SIGNAL)") (class "Default")
      (node (ref "J7") (pin "1") (pinfunction "SIGNAL_1") (pintype "passive"))
      (node (ref "L5") (pin "2") (pinfunction "2_2") (pintype "passive"))
      (node (ref "R82") (pin "2") (pintype "passive"))
    )
    (net (code "53") (name "Net-(J9-SIGNAL)") (class "Default")
      (node (ref "C78") (pin "2") (pinfunction "2_2") (pintype "passive"))
      (node (ref "J9") (pin "1") (pinfunction "SIGNAL_1") (pintype "passive"))
    )
    (net (code "54") (name "Net-(J11-SIGNAL)") (class "Default")
      (node (ref "J11") (pin "1") (pinfunction "SIGNAL_1") (pintype "passive"))
      (node (ref "L6") (pin "2") (pinfunction "2_2") (pintype "passive"))
      (node (ref "R90") (pin "2") (pintype "passive"))
    )
    (net (code "55") (name "Net-(J13-SIGNAL)") (class "Default")
      (node (ref "J13") (pin "1") (pinfunction "SIGNAL_1") (pintype "passive"))
      (node (ref "L7") (pin "2") (pinfunction "2_2") (pintype "passive"))
      (node (ref "R97") (pin "2") (pintype "passive"))
    )
    (net (code "56") (name "Net-(J14-SIGNAL)") (class "Default")
      (node (ref "C97") (pin "2") (pinfunction "2_2") (pintype "passive"))
      (node (ref "J14") (pin "1") (pinfunction "SIGNAL_1") (pintype "passive"))
    )
    (net (code "57") (name "Net-(J17-SIGNAL)") (class "Default")
      (node (ref "C114") (pin "2") (pinfunction "2_2") (pintype "passive"))
      (node (ref "J17") (pin "1") (pinfunction "SIGNAL_1") (pintype "passive"))
    )
    (net (code "58") (name "Net-(J18-SIGNAL)") (class "Default")
      (node (ref "J18") (pin "1") (pinfunction "SIGNAL_1") (pintype "passive"))
      (node (ref "L8") (pin "2") (pinfunction "2_2") (pintype "passive"))
      (node (ref "R110") (pin "2") (pintype "passive"))
    )
    (net (code "59") (name "Net-(U16-RSET)") (class "Default")
      (node (ref "R113") (pin "1") (pintype "passive"))
      (node (ref "U16") (pin "4") (pinfunction "RSET_4") (pintype "input"))
    )
    (net (code "60") (name "Net-(U16-SDO)") (class "Default")
      (node (ref "L1") (pin "1") (pinfunction "1_1") (pintype "passive"))
      (node (ref "R79") (pin "1") (pintype "passive"))
      (node (ref "R81") (pin "1") (pintype "passive"))
      (node (ref "U16") (pin "8") (pinfunction "SDO_8") (pintype "output"))
    )
    (net (code "61") (name "Net-(U16-~{SDO})") (class "Default")
      (node (ref "R118") (pin "2") (pintype "passive"))
      (node (ref "R80") (pin "1") (pintype "passive"))
      (node (ref "U16") (pin "7") (pinfunction "~{SDO}_7") (pintype "output"))
    )
    (net (code "62") (name "Net-(U17-RSET)") (class "Default")
      (node (ref "R114") (pin "1") (pintype "passive"))
      (node (ref "U17") (pin "4") (pinfunction "RSET_4") (pintype "input"))
    )
    (net (code "63") (name "Net-(U17-SDO)") (class "Default")
      (node (ref "L2") (pin "1") (pinfunction "1_1") (pintype "passive"))
      (node (ref "R87") (pin "1") (pintype "passive"))
      (node (ref "R89") (pin "1") (pintype "passive"))
      (node (ref "U17") (pin "8") (pinfunction "SDO_8") (pintype "output"))
    )
    (net (code "64") (name "Net-(U17-~{SDO})") (class "Default")
      (node (ref "R119") (pin "2") (pintype "passive"))
      (node (ref "R88") (pin "1") (pintype "passive"))
      (node (ref "U17") (pin "7") (pinfunction "~{SDO}_7") (pintype "output"))
    )
    (net (code "65") (name "Net-(U18-RSET)") (class "Default")
      (node (ref "R115") (pin "1") (pintype "passive"))
      (node (ref "U18") (pin "4") (pinfunction "RSET_4") (pintype "input"))
    )
    (net (code "66") (name "Net-(U18-SDO)") (class "Default")
      (node (ref "L3") (pin "1") (pinfunction "1_1") (pintype "passive"))
      (node (ref "R95") (pin "1") (pintype "passive"))
      (node (ref "R98") (pin "1") (pintype "passive"))
      (node (ref "U18") (pin "8") (pinfunction "SDO_8") (pintype "output"))
    )
    (net (code "67") (name "Net-(U18-~{SDO})") (class "Default")
      (node (ref "R121") (pin "2") (pintype "passive"))
      (node (ref "R96") (pin "1") (pintype "passive"))
      (node (ref "U18") (pin "7") (pinfunction "~{SDO}_7") (pintype "output"))
    )
    (net (code "68") (name "Net-(U19-RSET)") (class "Default")
      (node (ref "R116") (pin "1") (pintype "passive"))
      (node (ref "U19") (pin "4") (pinfunction "RSET_4") (pintype "input"))
    )
    (net (code "69") (name "Net-(U19-SDO)") (class "Default")
      (node (ref "L4") (pin "1") (pinfunction "1_1") (pintype "passive"))
      (node (ref "R108") (pin "1") (pintype "passive"))
      (node (ref "R59") (pin "1") (pintype "passive"))
      (node (ref "U19") (pin "8") (pinfunction "SDO_8") (pintype "output"))
    )
    (net (code "70") (name "Net-(U19-~{SDO})") (class "Default")
      (node (ref "R109") (pin "1") (pintype "passive"))
      (node (ref "R125") (pin "2") (pintype "passive"))
      (node (ref "U19") (pin "7") (pinfunction "~{SDO}_7") (pintype "output"))
    )
    (net (code "71") (name "Net-(U20-AGC+)") (class "Default")
      (node (ref "C134") (pin "1") (pinfunction "1_1") (pintype "passive"))
      (node (ref "U20") (pin "7") (pinfunction "AGC+_7") (pintype "passive"))
    )
    (net (code "72") (name "Net-(U20-AGC-)") (class "Default")
      (node (ref "C134") (pin "2") (pinfunction "2_2") (pintype "passive"))
      (node (ref "U20") (pin "8") (pinfunction "AGC-_8") (pintype "passive"))
    )
    (net (code "73") (name "Net-(U20-SDI)") (class "Default")
      (node (ref "C72") (pin "1") (pinfunction "1_1") (pintype "passive"))
      (node (ref "U20") (pin "4") (pinfunction "SDI_4") (pintype "input"))
    )
    (net (code "74") (name "Net-(U20-~{SDI})") (class "Default")
      (node (ref "C74") (pin "1") (pinfunction "1_1") (pintype "passive"))
      (node (ref "U20") (pin "5") (pinfunction "~{SDI}_5") (pintype "input"))
    )
    (net (code "75") (name "Net-(U21-AGC+)") (class "Default")
      (node (ref "C135") (pin "1") (pinfunction "1_1") (pintype "passive"))
      (node (ref "U21") (pin "7") (pinfunction "AGC+_7") (pintype "passive"))
    )
    (net (code "76") (name "Net-(U21-AGC-)") (class "Default")
      (node (ref "C135") (pin "2") (pinfunction "2_2") (pintype "passive"))
      (node (ref "U21") (pin "8") (pinfunction "AGC-_8") (pintype "passive"))
    )
    (net (code "77") (name "Net-(U21-SDI)") (class "Default")
      (node (ref "C82") (pin "1") (pinfunction "1_1") (pintype "passive"))
      (node (ref "U21") (pin "4") (pinfunction "SDI_4") (pintype "input"))
    )
    (net (code "78") (name "Net-(U21-~{SDI})") (class "Default")
      (node (ref "C86") (pin "1") (pinfunction "1_1") (pintype "passive"))
      (node (ref "U21") (pin "5") (pinfunction "~{SDI}_5") (pintype "input"))
    )
    (net (code "79") (name "Net-(U22-AGC+)") (class "Default")
      (node (ref "C136") (pin "1") (pinfunction "1_1") (pintype "passive"))
      (node (ref "U22") (pin "7") (pinfunction "AGC+_7") (pintype "passive"))
    )
    (net (code "80") (name "Net-(U22-AGC-)") (class "Default")
      (node (ref "C136") (pin "2") (pinfunction "2_2") (pintype "passive"))
      (node (ref "U22") (pin "8") (pinfunction "AGC-_8") (pintype "passive"))
    )
    (net (code "81") (name "Net-(U22-SDI)") (class "Default")
      (node (ref "C96") (pin "1") (pinfunction "1_1") (pintype "passive"))
      (node (ref "U22") (pin "4") (pinfunction "SDI_4") (pintype "input"))
    )
    (net (code "82") (name "Net-(U22-~{SDI})") (class "Default")
      (node (ref "C98") (pin "1") (pinfunction "1_1") (pintype "passive"))
      (node (ref "U22") (pin "5") (pinfunction "~{SDI}_5") (pintype "input"))
    )
    (net (code "83") (name "Net-(U23-AGC+)") (class "Default")
      (node (ref "C137") (pin "1") (pinfunction "1_1") (pintype "passive"))
      (node (ref "U23") (pin "7") (pinfunction "AGC+_7") (pintype "passive"))
    )
    (net (code "84") (name "Net-(U23-AGC-)") (class "Default")
      (node (ref "C137") (pin "2") (pinfunction "2_2") (pintype "passive"))
      (node (ref "U23") (pin "8") (pinfunction "AGC-_8") (pintype "passive"))
    )
    (net (code "85") (name "Net-(U23-SDI)") (class "Default")
      (node (ref "C115") (pin "1") (pinfunction "1_1") (pintype "passive"))
      (node (ref "U23") (pin "4") (pinfunction "SDI_4") (pintype "input"))
    )
    (net (code "86") (name "Net-(U23-~{SDI})") (class "Default")
      (node (ref "C117") (pin "1") (pinfunction "1_1") (pintype "passive"))
      (node (ref "U23") (pin "5") (pinfunction "~{SDI}_5") (pintype "input"))
    )
  )
)
